# SparkFun_SSOP16_Breakout_v10.net
KiCad netlist of a schematic drawn in EAGLE
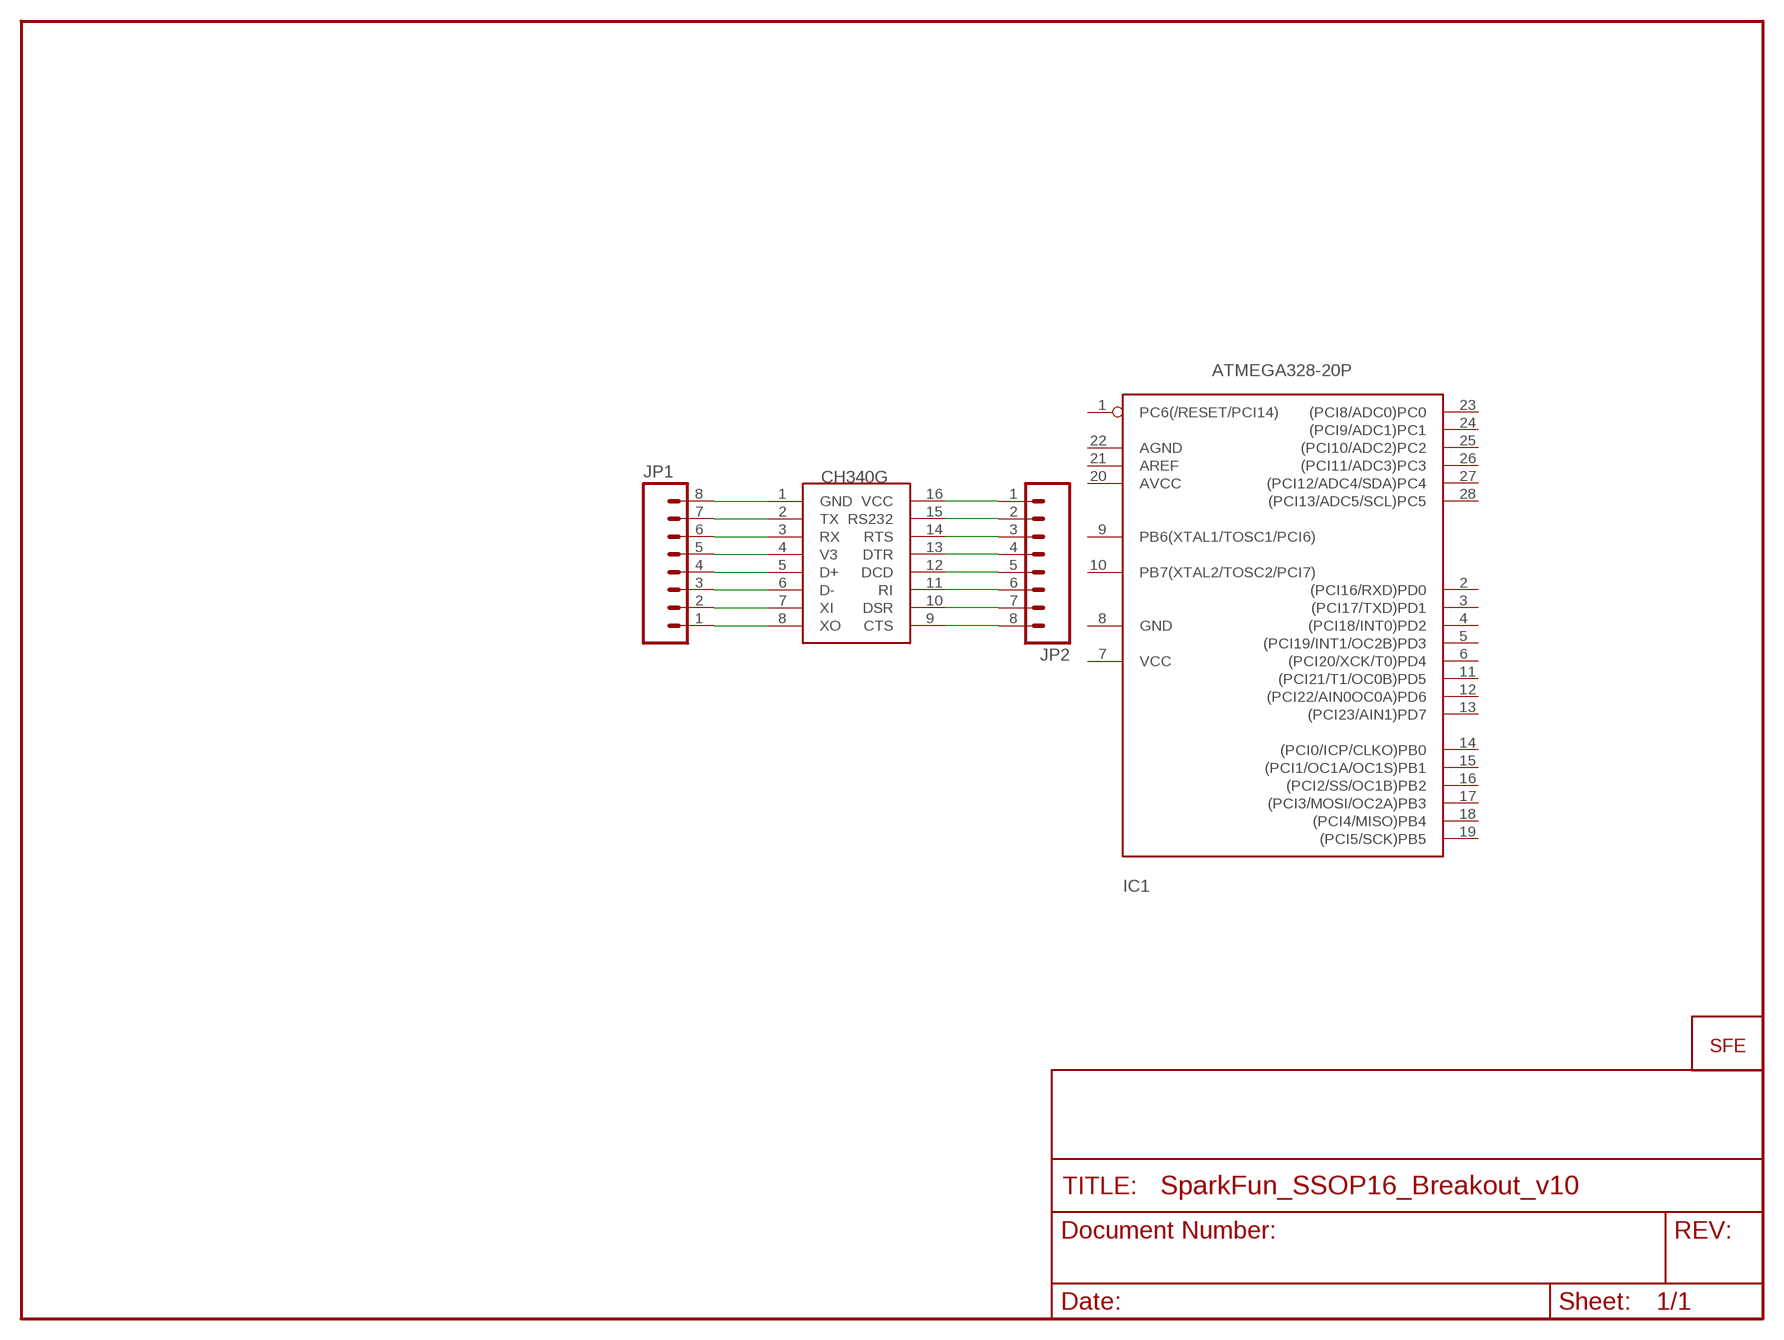
[diagram p0: schematic, sheet 1]

(export (version "E")
  (design (tool "Eeschema 10.0.6"))
  (components
    (comp (ref "IC1")
      (value "ATMEGA328-20P")
      (footprint "eagle-import:DIL28-3")
      (libsource (lib "eagle-import") (part "ATMEGA328P-20"))
    )
    (comp (ref "JP1")
      (value "M08")
      (footprint "eagle-import:1X08")
      (libsource (lib "eagle-import") (part "M08"))
    )
    (comp (ref "JP2")
      (value "M08")
      (footprint "eagle-import:1X08")
      (libsource (lib "eagle-import") (part "M08"))
    )
    (comp (ref "U$1")
      (value "LOGO-SFESK")
      (footprint "eagle-import:SFE-LOGO-FLAME")
      (libsource (lib "eagle-import") (part "LOGO-SFESK"))
    )
    (comp (ref "U$2")
      (value "CH340G")
      (footprint "eagle-import:SOIC16")
      (libsource (lib "eagle-import") (part "CH340G"))
    )
  )
  (nets
    (net (code "1") (name "Net-(U$2-CTS)") (class "Default")
      (node (ref "JP2") (pin "8") (pinfunction "8_8") (pintype "passive"))
      (node (ref "U$2") (pin "9") (pinfunction "CTS_9") (pintype "bidirectional"))
    )
    (net (code "2") (name "Net-(U$2-D+)") (class "Default")
      (node (ref "JP1") (pin "4") (pinfunction "4_4") (pintype "passive"))
      (node (ref "U$2") (pin "5") (pinfunction "D+_5") (pintype "bidirectional"))
    )
    (net (code "3") (name "Net-(U$2-D-)") (class "Default")
      (node (ref "JP1") (pin "3") (pinfunction "3_3") (pintype "passive"))
      (node (ref "U$2") (pin "6") (pinfunction "D-_6") (pintype "bidirectional"))
    )
    (net (code "4") (name "Net-(U$2-DCD)") (class "Default")
      (node (ref "JP2") (pin "5") (pinfunction "5_5") (pintype "passive"))
      (node (ref "U$2") (pin "12") (pinfunction "DCD_12") (pintype "bidirectional"))
    )
    (net (code "5") (name "Net-(U$2-DSR)") (class "Default")
      (node (ref "JP2") (pin "7") (pinfunction "7_7") (pintype "passive"))
      (node (ref "U$2") (pin "10") (pinfunction "DSR_10") (pintype "bidirectional"))
    )
    (net (code "6") (name "Net-(U$2-DTR)") (class "Default")
      (node (ref "JP2") (pin "4") (pinfunction "4_4") (pintype "passive"))
      (node (ref "U$2") (pin "13") (pinfunction "DTR_13") (pintype "bidirectional"))
    )
    (net (code "7") (name "Net-(U$2-GND)") (class "Default")
      (node (ref "JP1") (pin "8") (pinfunction "8_8") (pintype "passive"))
      (node (ref "U$2") (pin "1") (pinfunction "GND_1") (pintype "bidirectional"))
    )
    (net (code "8") (name "Net-(U$2-RI)") (class "Default")
      (node (ref "JP2") (pin "6") (pinfunction "6_6") (pintype "passive"))
      (node (ref "U$2") (pin "11") (pinfunction "RI_11") (pintype "bidirectional"))
    )
    (net (code "9") (name "Net-(U$2-RS232)") (class "Default")
      (node (ref "JP2") (pin "2") (pinfunction "2_2") (pintype "passive"))
      (node (ref "U$2") (pin "15") (pinfunction "RS232_15") (pintype "bidirectional"))
    )
    (net (code "10") (name "Net-(U$2-RTS)") (class "Default")
      (node (ref "JP2") (pin "3") (pinfunction "3_3") (pintype "passive"))
      (node (ref "U$2") (pin "14") (pinfunction "RTS_14") (pintype "bidirectional"))
    )
    (net (code "11") (name "Net-(U$2-RX)") (class "Default")
      (node (ref "JP1") (pin "6") (pinfunction "6_6") (pintype "passive"))
      (node (ref "U$2") (pin "3") (pinfunction "RX_3") (pintype "bidirectional"))
    )
    (net (code "12") (name "Net-(U$2-TX)") (class "Default")
      (node (ref "JP1") (pin "7") (pinfunction "7_7") (pintype "passive"))
      (node (ref "U$2") (pin "2") (pinfunction "TX_2") (pintype "bidirectional"))
    )
    (net (code "13") (name "Net-(U$2-V3)") (class "Default")
      (node (ref "JP1") (pin "5") (pinfunction "5_5") (pintype "passive"))
      (node (ref "U$2") (pin "4") (pinfunction "V3_4") (pintype "bidirectional"))
    )
    (net (code "14") (name "Net-(U$2-VCC)") (class "Default")
      (node (ref "JP2") (pin "1") (pinfunction "1_1") (pintype "passive"))
      (node (ref "U$2") (pin "16") (pinfunction "VCC_16") (pintype "bidirectional"))
    )
    (net (code "15") (name "Net-(U$2-XI)") (class "Default")
      (node (ref "JP1") (pin "2") (pinfunction "2_2") (pintype "passive"))
      (node (ref "U$2") (pin "7") (pinfunction "XI_7") (pintype "bidirectional"))
    )
    (net (code "16") (name "Net-(U$2-XO)") (class "Default")
      (node (ref "JP1") (pin "1") (pinfunction "1_1") (pintype "passive"))
      (node (ref "U$2") (pin "8") (pinfunction "XO_8") (pintype "bidirectional"))
    )
    (net (code "17") (name "unconnected-(IC1-(PCI0{slash}ICP{slash}CLKO)PB0-Pad14)") (class "Default")
      (node (ref "IC1") (pin "14") (pinfunction "(PCI0/ICP/CLKO)PB0_14") (pintype "bidirectional"))
    )
    (net (code "18") (name "unconnected-(IC1-(PCI1{slash}OC1A{slash}OC1S)PB1-Pad15)") (class "Default")
      (node (ref "IC1") (pin "15") (pinfunction "(PCI1/OC1A/OC1S)PB1_15") (pintype "bidirectional"))
    )
    (net (code "19") (name "unconnected-(IC1-(PCI2{slash}SS{slash}OC1B)PB2-Pad16)") (class "Default")
      (node (ref "IC1") (pin "16") (pinfunction "(PCI2/SS/OC1B)PB2_16") (pintype "bidirectional"))
    )
    (net (code "20") (name "unconnected-(IC1-(PCI3{slash}MOSI{slash}OC2A)PB3-Pad17)") (class "Default")
      (node (ref "IC1") (pin "17") (pinfunction "(PCI3/MOSI/OC2A)PB3_17") (pintype "bidirectional"))
    )
    (net (code "21") (name "unconnected-(IC1-(PCI4{slash}MISO)PB4-Pad18)") (class "Default")
      (node (ref "IC1") (pin "18") (pinfunction "(PCI4/MISO)PB4_18") (pintype "bidirectional"))
    )
    (net (code "22") (name "unconnected-(IC1-(PCI5{slash}SCK)PB5-Pad19)") (class "Default")
      (node (ref "IC1") (pin "19") (pinfunction "(PCI5/SCK)PB5_19") (pintype "bidirectional"))
    )
    (net (code "23") (name "unconnected-(IC1-(PCI8{slash}ADC0)PC0-Pad23)") (class "Default")
      (node (ref "IC1") (pin "23") (pinfunction "(PCI8/ADC0)PC0_23") (pintype "bidirectional"))
    )
    (net (code "24") (name "unconnected-(IC1-(PCI9{slash}ADC1)PC1-Pad24)") (class "Default")
      (node (ref "IC1") (pin "24") (pinfunction "(PCI9/ADC1)PC1_24") (pintype "bidirectional"))
    )
    (net (code "25") (name "unconnected-(IC1-(PCI10{slash}ADC2)PC2-Pad25)") (class "Default")
      (node (ref "IC1") (pin "25") (pinfunction "(PCI10/ADC2)PC2_25") (pintype "bidirectional"))
    )
    (net (code "26") (name "unconnected-(IC1-(PCI11{slash}ADC3)PC3-Pad26)") (class "Default")
      (node (ref "IC1") (pin "26") (pinfunction "(PCI11/ADC3)PC3_26") (pintype "bidirectional"))
    )
    (net (code "27") (name "unconnected-(IC1-(PCI12{slash}ADC4{slash}SDA)PC4-Pad27)") (class "Default")
      (node (ref "IC1") (pin "27") (pinfunction "(PCI12/ADC4/SDA)PC4_27") (pintype "bidirectional"))
    )
    (net (code "28") (name "unconnected-(IC1-(PCI13{slash}ADC5{slash}SCL)PC5-Pad28)") (class "Default")
      (node (ref "IC1") (pin "28") (pinfunction "(PCI13/ADC5/SCL)PC5_28") (pintype "bidirectional"))
    )
    (net (code "29") (name "unconnected-(IC1-(PCI16{slash}RXD)PD0-Pad2)") (class "Default")
      (node (ref "IC1") (pin "2") (pinfunction "(PCI16/RXD)PD0_2") (pintype "bidirectional"))
    )
    (net (code "30") (name "unconnected-(IC1-(PCI17{slash}TXD)PD1-Pad3)") (class "Default")
      (node (ref "IC1") (pin "3") (pinfunction "(PCI17/TXD)PD1_3") (pintype "bidirectional"))
    )
    (net (code "31") (name "unconnected-(IC1-(PCI18{slash}INT0)PD2-Pad4)") (class "Default")
      (node (ref "IC1") (pin "4") (pinfunction "(PCI18/INT0)PD2_4") (pintype "bidirectional"))
    )
    (net (code "32") (name "unconnected-(IC1-(PCI19{slash}INT1{slash}OC2B)PD3-Pad5)") (class "Default")
      (node (ref "IC1") (pin "5") (pinfunction "(PCI19/INT1/OC2B)PD3_5") (pintype "bidirectional"))
    )
    (net (code "33") (name "unconnected-(IC1-(PCI20{slash}XCK{slash}T0)PD4-Pad6)") (class "Default")
      (node (ref "IC1") (pin "6") (pinfunction "(PCI20/XCK/T0)PD4_6") (pintype "bidirectional"))
    )
    (net (code "34") (name "unconnected-(IC1-(PCI21{slash}T1{slash}OC0B)PD5-Pad11)") (class "Default")
      (node (ref "IC1") (pin "11") (pinfunction "(PCI21/T1/OC0B)PD5_11") (pintype "bidirectional"))
    )
    (net (code "35") (name "unconnected-(IC1-(PCI22{slash}AIN0OC0A)PD6-Pad12)") (class "Default")
      (node (ref "IC1") (pin "12") (pinfunction "(PCI22/AIN0OC0A)PD6_12") (pintype "bidirectional"))
    )
    (net (code "36") (name "unconnected-(IC1-(PCI23{slash}AIN1)PD7-Pad13)") (class "Default")
      (node (ref "IC1") (pin "13") (pinfunction "(PCI23/AIN1)PD7_13") (pintype "bidirectional"))
    )
    (net (code "37") (name "unconnected-(IC1-AGND-Pad22)") (class "Default")
      (node (ref "IC1") (pin "22") (pinfunction "AGND_22") (pintype "bidirectional"))
    )
    (net (code "38") (name "unconnected-(IC1-AREF-Pad21)") (class "Default")
      (node (ref "IC1") (pin "21") (pinfunction "AREF_21") (pintype "bidirectional"))
    )
    (net (code "39") (name "unconnected-(IC1-AVCC-Pad20)") (class "Default")
      (node (ref "IC1") (pin "20") (pinfunction "AVCC_20") (pintype "bidirectional"))
    )
    (net (code "40") (name "unconnected-(IC1-GND-Pad8)") (class "Default")
      (node (ref "IC1") (pin "8") (pinfunction "GND_8") (pintype "bidirectional"))
    )
    (net (code "41") (name "unconnected-(IC1-PB6(XTAL1{slash}TOSC1{slash}PCI6)-Pad9)") (class "Default")
      (node (ref "IC1") (pin "9") (pinfunction "PB6(XTAL1/TOSC1/PCI6)_9") (pintype "bidirectional"))
    )
    (net (code "42") (name "unconnected-(IC1-PB7(XTAL2{slash}TOSC2{slash}PCI7)-Pad10)") (class "Default")
      (node (ref "IC1") (pin "10") (pinfunction "PB7(XTAL2/TOSC2/PCI7)_10") (pintype "bidirectional"))
    )
    (net (code "43") (name "unconnected-(IC1-PC6({slash}RESET{slash}PCI14)-Pad1)") (class "Default")
      (node (ref "IC1") (pin "1") (pinfunction "PC6(/RESET/PCI14)_1") (pintype "bidirectional"))
    )
    (net (code "44") (name "unconnected-(IC1-VCC-Pad7)") (class "Default")
      (node (ref "IC1") (pin "7") (pinfunction "VCC_7") (pintype "bidirectional"))
    )
  )
)
